# KDAT_Sch.net
KiCad netlist of a schematic drawn in Altium Designer
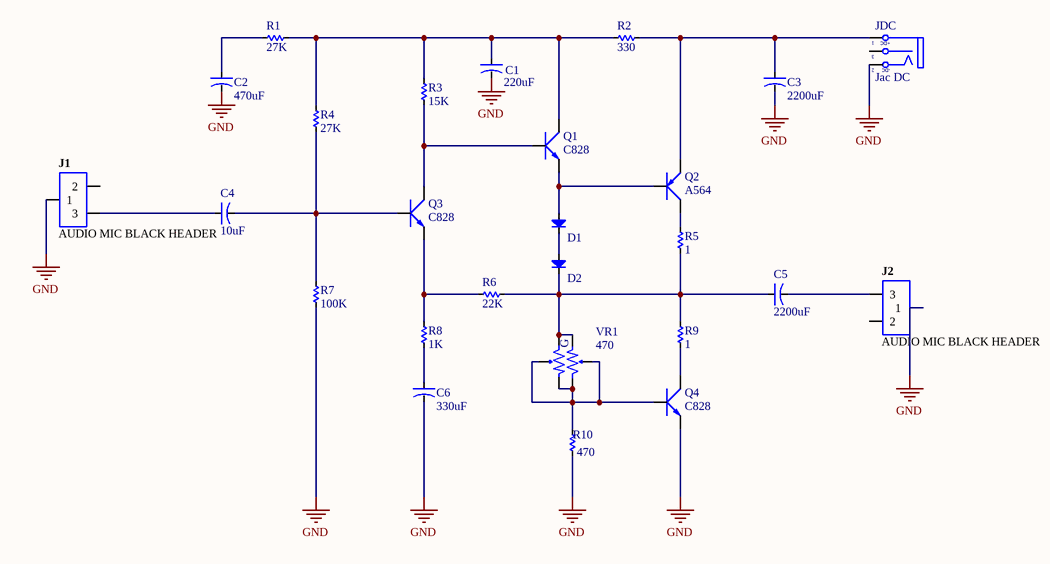
[diagram p0: KDAT_Sch.SchDoc]

(export (version "E")
  (design (tool "Eeschema 10.0.6"))
  (components
    (comp (ref "C1")
      (value "220uF")
      (footprint "CA-ALU-6.3")
      (description "Capacitor (Semiconductor SIM Model)")
      (fields (field (name "PUBLISHER") "Altium Limited"))
      (libsource (lib "Altium Library") (part "CN-ALU-DIP"))
    )
    (comp (ref "C2")
      (value "470uF")
      (footprint "CA-ALU-6.3")
      (description "Capacitor (Semiconductor SIM Model)")
      (fields (field (name "PUBLISHER") "Altium Limited"))
      (libsource (lib "Altium Library") (part "CN-ALU-DIP"))
    )
    (comp (ref "C3")
      (value "2200uF")
      (footprint "CA-ALU-10")
      (description "Capacitor (Semiconductor SIM Model)")
      (fields (field (name "PUBLISHER") "Altium Limited"))
      (libsource (lib "Altium Library") (part "CN-ALU-DIP"))
    )
    (comp (ref "C4")
      (value "10uF")
      (footprint "CA-ALU-6.3")
      (description "Capacitor (Semiconductor SIM Model)")
      (fields (field (name "PUBLISHER") "Altium Limited"))
      (libsource (lib "Altium Library") (part "CN-ALU-DIP"))
    )
    (comp (ref "C5")
      (value "2200uF")
      (footprint "CA-ALU-10")
      (description "Capacitor (Semiconductor SIM Model)")
      (fields (field (name "PUBLISHER") "Altium Limited"))
      (libsource (lib "Altium Library") (part "CN-ALU-DIP"))
    )
    (comp (ref "C6")
      (value "330uF")
      (footprint "CA-ALU-6.3")
      (description "Capacitor (Semiconductor SIM Model)")
      (fields (field (name "PUBLISHER") "Altium Limited"))
      (libsource (lib "Altium Library") (part "CN-ALU-DIP"))
    )
    (comp (ref "D1")
      (value "1N4148")
      (footprint "DIO-0.5A-SMALL")
      (description "Default Diode")
      (fields (field (name "PUBLISHER") "Altium Limited"))
      (libsource (lib "Altium Library") (part "Diode"))
    )
    (comp (ref "D2")
      (value "1N4148")
      (footprint "DIO-0.5A-SMALL")
      (description "Default Diode")
      (fields (field (name "PUBLISHER") "Altium Limited"))
      (libsource (lib "Altium Library") (part "Diode"))
    )
    (comp (ref "J1")
      (value "AUDIO MIC BLACK HEADER")
      (footprint "CON MIC2")
      (libsource (lib "Altium Library") (part "CON MIC2"))
    )
    (comp (ref "J2")
      (value "AUDIO MIC BLACK HEADER")
      (footprint "CON MIC2")
      (libsource (lib "Altium Library") (part "CON MIC2"))
    )
    (comp (ref "JDC")
      (value "Jac DC")
      (footprint "DC0")
      (description "Jac DC input")
      (libsource (lib "Altium Library") (part "DCIN"))
    )
    (comp (ref "Q1")
      (value "C828")
      (footprint "TO92-123")
      (description "NPN 600mW, ECB")
      (libsource (lib "Altium Library") (part "2N222"))
    )
    (comp (ref "Q2")
      (value "A564")
      (footprint "TO92-123")
      (description "PNP 600mW, ECB")
      (libsource (lib "Altium Library") (part "2N3906"))
    )
    (comp (ref "Q3")
      (value "C828")
      (footprint "TO92-123")
      (description "NPN 600mW, ECB")
      (libsource (lib "Altium Library") (part "2N222"))
    )
    (comp (ref "Q4")
      (value "C828")
      (footprint "TO92-123")
      (description "NPN 600mW, ECB")
      (libsource (lib "Altium Library") (part "2N222"))
    )
    (comp (ref "R1")
      (value "27K")
      (footprint "RES-1/4WD")
      (description "Res")
      (fields
        (field (name "MANUFACTURER") "Generic Components")
        (field (name "PUBLISHER") "Altium Hobart Technology Centre")
      )
      (libsource (lib "Altium Library") (part "Res"))
    )
    (comp (ref "R2")
      (value "330")
      (footprint "RES-1/4WD")
      (description "Res")
      (fields
        (field (name "MANUFACTURER") "Generic Components")
        (field (name "PUBLISHER") "Altium Hobart Technology Centre")
      )
      (libsource (lib "Altium Library") (part "Res"))
    )
    (comp (ref "R3")
      (value "15K")
      (footprint "RES-1/4WD")
      (description "Res")
      (fields
        (field (name "MANUFACTURER") "Generic Components")
        (field (name "PUBLISHER") "Altium Hobart Technology Centre")
      )
      (libsource (lib "Altium Library") (part "Res"))
    )
    (comp (ref "R4")
      (value "27K")
      (footprint "RES-1/4WD")
      (description "Res")
      (fields
        (field (name "MANUFACTURER") "Generic Components")
        (field (name "PUBLISHER") "Altium Hobart Technology Centre")
      )
      (libsource (lib "Altium Library") (part "Res"))
    )
    (comp (ref "R5")
      (value "1")
      (footprint "RES-1/4WD")
      (description "Res")
      (fields
        (field (name "MANUFACTURER") "Generic Components")
        (field (name "PUBLISHER") "Altium Hobart Technology Centre")
      )
      (libsource (lib "Altium Library") (part "Res"))
    )
    (comp (ref "R6")
      (value "22K")
      (footprint "RES-1/4WD")
      (description "Res")
      (fields
        (field (name "MANUFACTURER") "Generic Components")
        (field (name "PUBLISHER") "Altium Hobart Technology Centre")
      )
      (libsource (lib "Altium Library") (part "Res"))
    )
    (comp (ref "R7")
      (value "100K")
      (footprint "RES-1/4WD")
      (description "Res")
      (fields
        (field (name "MANUFACTURER") "Generic Components")
        (field (name "PUBLISHER") "Altium Hobart Technology Centre")
      )
      (libsource (lib "Altium Library") (part "Res"))
    )
    (comp (ref "R8")
      (value "1K")
      (footprint "RES-1/4WD")
      (description "Res")
      (fields
        (field (name "MANUFACTURER") "Generic Components")
        (field (name "PUBLISHER") "Altium Hobart Technology Centre")
      )
      (libsource (lib "Altium Library") (part "Res"))
    )
    (comp (ref "R9")
      (value "1")
      (footprint "RES-1/4WD")
      (description "Res")
      (fields
        (field (name "MANUFACTURER") "Generic Components")
        (field (name "PUBLISHER") "Altium Hobart Technology Centre")
      )
      (libsource (lib "Altium Library") (part "Res"))
    )
    (comp (ref "R10")
      (value "470")
      (footprint "RES-1/4WD")
      (description "Res")
      (fields
        (field (name "MANUFACTURER") "Generic Components")
        (field (name "PUBLISHER") "Altium Hobart Technology Centre")
      )
      (libsource (lib "Altium Library") (part "Res"))
    )
    (comp (ref "VR1")
      (value "470")
      (footprint "VR-D1")
      (description "Volume control Dual")
      (libsource (lib "Altium Library") (part "VR-D"))
    )
  )
  (nets
    (net (code "1") (name "GND") (class "Default")
      (node (ref "C1") (pin "2") (pinfunction "2_2") (pintype "passive"))
      (node (ref "C2") (pin "2") (pinfunction "2_2") (pintype "passive"))
      (node (ref "C3") (pin "2") (pinfunction "2_2") (pintype "passive"))
      (node (ref "C6") (pin "2") (pinfunction "2_2") (pintype "passive"))
      (node (ref "J1") (pin "1") (pinfunction "1_1") (pintype "passive"))
      (node (ref "J2") (pin "1") (pinfunction "1_1") (pintype "passive"))
      (node (ref "JDC") (pin "2") (pinfunction "TN_2") (pintype "passive"))
      (node (ref "Q4") (pin "1") (pinfunction "E_1") (pintype "passive"))
      (node (ref "R10") (pin "1") (pinfunction "1_1") (pintype "passive"))
      (node (ref "R7") (pin "2") (pinfunction "2_2") (pintype "passive"))
    )
    (net (code "2") (name "Net-(C2-Pad1)") (class "Default")
      (node (ref "C2") (pin "1") (pinfunction "1_1") (pintype "passive"))
      (node (ref "R1") (pin "2") (pinfunction "2_2") (pintype "passive"))
    )
    (net (code "3") (name "Net-(C4-Pad1)") (class "Default")
      (node (ref "C4") (pin "1") (pinfunction "1_1") (pintype "passive"))
      (node (ref "J1") (pin "3") (pinfunction "3_3") (pintype "passive"))
    )
    (net (code "4") (name "Net-(C5-Pad2)") (class "Default")
      (node (ref "C5") (pin "2") (pinfunction "2_2") (pintype "passive"))
      (node (ref "J2") (pin "3") (pinfunction "3_3") (pintype "passive"))
    )
    (net (code "5") (name "Net-(C6-Pad1)") (class "Default")
      (node (ref "C6") (pin "1") (pinfunction "1_1") (pintype "passive"))
      (node (ref "R8") (pin "2") (pinfunction "2_2") (pintype "passive"))
    )
    (net (code "6") (name "Net-(D1-A)") (class "Default")
      (node (ref "D1") (pin "1") (pinfunction "A_1") (pintype "passive"))
      (node (ref "Q1") (pin "1") (pinfunction "E_1") (pintype "passive"))
      (node (ref "Q2") (pin "2") (pinfunction "B_2") (pintype "passive"))
    )
    (net (code "7") (name "Net-(D1-K)") (class "Default")
      (node (ref "D1") (pin "2") (pinfunction "K_2") (pintype "passive"))
      (node (ref "D2") (pin "1") (pinfunction "A_1") (pintype "passive"))
    )
    (net (code "8") (name "Net-(D2-K)") (class "Default")
      (node (ref "C5") (pin "1") (pinfunction "1_1") (pintype "passive"))
      (node (ref "D2") (pin "2") (pinfunction "K_2") (pintype "passive"))
      (node (ref "R5") (pin "1") (pinfunction "1_1") (pintype "passive"))
      (node (ref "R6") (pin "2") (pinfunction "2_2") (pintype "passive"))
      (node (ref "R9") (pin "2") (pinfunction "2_2") (pintype "passive"))
      (node (ref "VR1") (pin "1") (pinfunction "1_1") (pintype "passive"))
      (node (ref "VR1") (pin "4") (pinfunction "4_4") (pintype "passive"))
    )
    (net (code "9") (name "Net-(JDC-T)") (class "Default")
      (node (ref "C3") (pin "1") (pinfunction "1_1") (pintype "passive"))
      (node (ref "JDC") (pin "1") (pinfunction "T_1") (pintype "passive"))
      (node (ref "Q2") (pin "1") (pinfunction "E_1") (pintype "passive"))
      (node (ref "R2") (pin "2") (pinfunction "2_2") (pintype "passive"))
    )
    (net (code "10") (name "Net-(Q1-B)") (class "Default")
      (node (ref "Q1") (pin "2") (pinfunction "B_2") (pintype "passive"))
      (node (ref "Q3") (pin "3") (pinfunction "C_3") (pintype "passive"))
      (node (ref "R3") (pin "2") (pinfunction "2_2") (pintype "passive"))
    )
    (net (code "11") (name "Net-(Q1-C)") (class "Default")
      (node (ref "C1") (pin "1") (pinfunction "1_1") (pintype "passive"))
      (node (ref "Q1") (pin "3") (pinfunction "C_3") (pintype "passive"))
      (node (ref "R1") (pin "1") (pinfunction "1_1") (pintype "passive"))
      (node (ref "R2") (pin "1") (pinfunction "1_1") (pintype "passive"))
      (node (ref "R3") (pin "1") (pinfunction "1_1") (pintype "passive"))
      (node (ref "R4") (pin "1") (pinfunction "1_1") (pintype "passive"))
    )
    (net (code "12") (name "Net-(Q2-C)") (class "Default")
      (node (ref "Q2") (pin "3") (pinfunction "C_3") (pintype "passive"))
      (node (ref "R5") (pin "2") (pinfunction "2_2") (pintype "passive"))
    )
    (net (code "13") (name "Net-(Q3-B)") (class "Default")
      (node (ref "C4") (pin "2") (pinfunction "2_2") (pintype "passive"))
      (node (ref "Q3") (pin "2") (pinfunction "B_2") (pintype "passive"))
      (node (ref "R4") (pin "2") (pinfunction "2_2") (pintype "passive"))
      (node (ref "R7") (pin "1") (pinfunction "1_1") (pintype "passive"))
    )
    (net (code "14") (name "Net-(Q3-E)") (class "Default")
      (node (ref "Q3") (pin "1") (pinfunction "E_1") (pintype "passive"))
      (node (ref "R6") (pin "1") (pinfunction "1_1") (pintype "passive"))
      (node (ref "R8") (pin "1") (pinfunction "1_1") (pintype "passive"))
    )
    (net (code "15") (name "Net-(Q4-B)") (class "Default")
      (node (ref "Q4") (pin "2") (pinfunction "B_2") (pintype "passive"))
      (node (ref "R10") (pin "2") (pinfunction "2_2") (pintype "passive"))
      (node (ref "VR1") (pin "2") (pinfunction "2_2") (pintype "passive"))
      (node (ref "VR1") (pin "3") (pinfunction "3_3") (pintype "passive"))
      (node (ref "VR1") (pin "5") (pinfunction "5_5") (pintype "passive"))
      (node (ref "VR1") (pin "6") (pinfunction "6_6") (pintype "passive"))
    )
    (net (code "16") (name "Net-(Q4-C)") (class "Default")
      (node (ref "Q4") (pin "3") (pinfunction "C_3") (pintype "passive"))
      (node (ref "R9") (pin "1") (pinfunction "1_1") (pintype "passive"))
    )
    (net (code "17") (name "unconnected-(J1-Pad2)") (class "Default")
      (node (ref "J1") (pin "2") (pinfunction "2_2") (pintype "passive"))
    )
    (net (code "18") (name "unconnected-(J2-Pad2)") (class "Default")
      (node (ref "J2") (pin "2") (pinfunction "2_2") (pintype "passive"))
    )
    (net (code "19") (name "unconnected-(JDC-S-Pad3)") (class "Default")
      (node (ref "JDC") (pin "3") (pinfunction "S_3") (pintype "power_in"))
    )
  )
)
